# MCU.net
KiCad netlist of a schematic drawn in Altium Designer
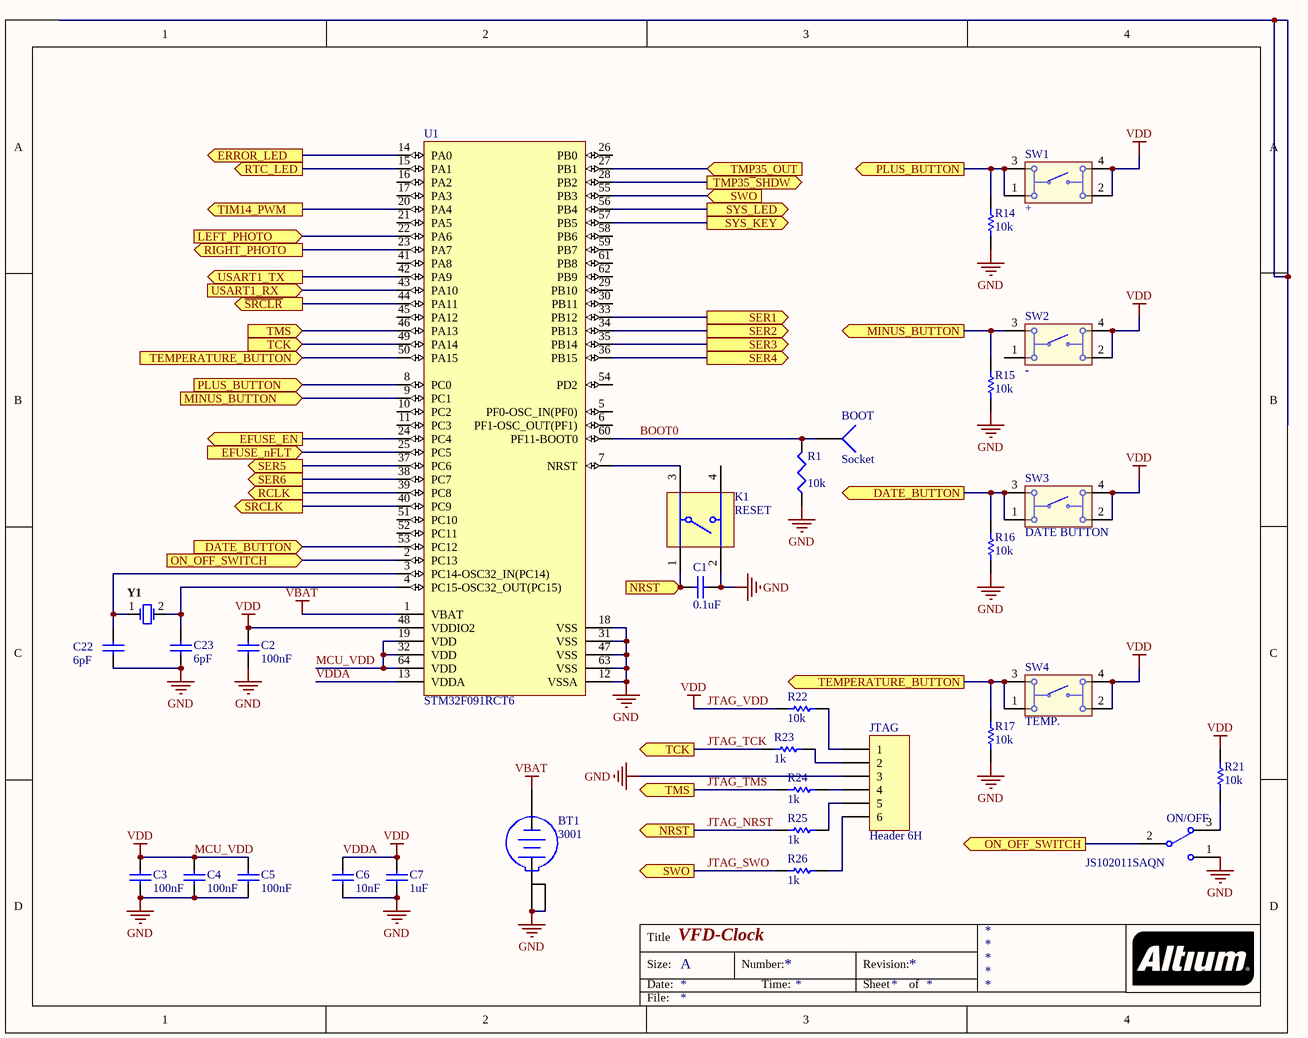
[diagram p0: MCU.SchDoc]

(export (version "E")
  (design (tool "Eeschema 10.0.6"))
  (components
    (comp (ref "BOOT")
      (value "Socket")
      (footprint "PIN1")
      (fields (field (name "PUBLISHER") "Altium Limited"))
      (libsource (lib "Miscellaneous Connectors") (part "Socket"))
    )
    (comp (ref "BT1")
      (value "3001")
      (footprint "KSTN-3001_V")
      (description "Holder Battery Coin, 12 mm, 2-Pin THD, RoHS")
      (fields (field (name "MANUFACTURER") "Keystone"))
      (libsource (lib "Altium Content Vault") (part "BATTERY-HOLDER-COIN-3"))
    )
    (comp (ref "C1")
      (value "0.1uF")
      (footprint "CAPC1608X90X40ML10T20")
      (fields (field (name "TOLERANCE") "±10%") (field (name "MANUFACTURER") "Yageo"))
      (libsource (lib "Altium Content Vault") (part "CAP-NP-2"))
    )
    (comp (ref "C2")
      (value "100nF")
      (footprint "CAPC1608X90X40ML10T20")
      (fields (field (name "TOLERANCE") "±10%") (field (name "MANUFACTURER") "Yageo"))
      (libsource (lib "Altium Content Vault") (part "CAP-NP-2"))
    )
    (comp (ref "C3")
      (value "100nF")
      (footprint "CAPC1608X90X40ML10T20")
      (fields (field (name "TOLERANCE") "±10%") (field (name "MANUFACTURER") "Yageo"))
      (libsource (lib "Altium Content Vault") (part "CAP-NP-2"))
    )
    (comp (ref "C4")
      (value "100nF")
      (footprint "CAPC1608X90X40ML10T20")
      (fields (field (name "TOLERANCE") "±10%") (field (name "MANUFACTURER") "Yageo"))
      (libsource (lib "Altium Content Vault") (part "CAP-NP-2"))
    )
    (comp (ref "C5")
      (value "100nF")
      (footprint "CAPC1608X90X40ML10T20")
      (fields (field (name "TOLERANCE") "±10%") (field (name "MANUFACTURER") "Yageo"))
      (libsource (lib "Altium Content Vault") (part "CAP-NP-2"))
    )
    (comp (ref "C6")
      (value "10nF")
      (footprint "CAPC1608X90X40ML10T20")
      (description "Chip Capacitor, 10 nF, +/- 10%, 50 V, -55 to 125 degC, 0603 (1608 Metric), RoHS, Tape and Reel")
      (fields (field (name "MANUFACTURER") "Yageo") (field (name "TOLERANCE") "10%"))
      (libsource (lib "Altium Content Vault") (part "CAP-NP-2"))
    )
    (comp (ref "C7")
      (value "1uF")
      (footprint "CAPC1608X90X20LL10")
      (description "Chip Capacitor, 1 uF, +/- 10%, 50 V, -55 to 85 degC, 0603 (1608 Metric), RoHS, Tape and Reel")
      (fields
        (field (name "MANUFACTURER") "TDK")
        (field (name "PCN PART NUMBER") "MLCCPartNumberChange30/Nov/2012")
      )
      (libsource (lib "Altium Content Vault") (part "CAP-NP-2"))
    )
    (comp (ref "C22")
      (value "6pF")
      (footprint "CAPC1608X90X40ML10T20")
      (fields (field (name "TOLERANCE") "±10%") (field (name "MANUFACTURER") "Yageo"))
      (libsource (lib "Altium Content Vault") (part "CAP-NP-2"))
    )
    (comp (ref "C23")
      (value "6pF")
      (footprint "CAPC1608X90X40ML10T20")
      (fields (field (name "TOLERANCE") "±10%") (field (name "MANUFACTURER") "Yageo"))
      (libsource (lib "Altium Content Vault") (part "CAP-NP-2"))
    )
    (comp (ref "JTAG")
      (value "Header 6H")
      (footprint "HDR1X6H")
      (description "Header, 6-Pin, Right Angle")
      (fields (field (name "PUBLISHER") "Altium Limited"))
      (libsource (lib "Miscellaneous Connectors") (part "Header 6H"))
    )
    (comp (ref "K1")
      (value "RESET")
      (footprint "PNSC-EVPAA_V")
      (description "Light Touch Switch, 100 mOhm, -40 to 85 degC, 4-Pin SMD, RoHS, Tape and Reel")
      (fields (field (name "MANUFACTURER") "Panasonic") (field (name "PART NO") "EVP-AA002K"))
      (libsource (lib "VFD_Clock_lib") (part "CMP-2000-06231-1"))
    )
    (comp (ref "ON/OFF")
      (value "JS102011SAQN")
      (footprint "CKCP-JS102011SAQN-3_V")
      (description "Sub-Miniature Slide Switch, SPDT, -40 to 85 degC, 3-Pin SMD, RoHS, Tape and Reel")
      (fields (field (name "MANUFACTURER") "C&K Components"))
      (libsource (lib "Altium Content Vault") (part "SW-SPDT-3"))
    )
    (comp (ref "R1")
      (value "10k")
      (footprint "J1-0603")
      (description "Resistor")
      (fields (field (name "PUBLISHER") "Altium Limited"))
      (libsource (lib "Miscellaneous Devices") (part "Res3"))
    )
    (comp (ref "R14")
      (value "10k")
      (footprint "RESC1608X55X30LL20T20")
      (fields (field (name "MANUFACTURER") "Panasonic") (field (name "PART NUMBER") "ERA3AEB102V"))
      (libsource (lib "Altium Content Vault") (part "RES"))
    )
    (comp (ref "R15")
      (value "10k")
      (footprint "RESC1608X55X30LL20T20")
      (fields (field (name "MANUFACTURER") "Panasonic") (field (name "PART NUMBER") "ERA3AEB102V"))
      (libsource (lib "Altium Content Vault") (part "RES"))
    )
    (comp (ref "R16")
      (value "10k")
      (footprint "RESC1608X55X30LL20T20")
      (fields (field (name "MANUFACTURER") "Panasonic") (field (name "PART NUMBER") "ERA3AEB102V"))
      (libsource (lib "Altium Content Vault") (part "RES"))
    )
    (comp (ref "R17")
      (value "10k")
      (footprint "RESC1608X55X30LL20T20")
      (fields (field (name "MANUFACTURER") "Panasonic") (field (name "PART NUMBER") "ERA3AEB102V"))
      (libsource (lib "Altium Content Vault") (part "RES"))
    )
    (comp (ref "R21")
      (value "10k")
      (footprint "RESC1608X55X30LL20T20")
      (fields (field (name "MANUFACTURER") "Panasonic") (field (name "PART NUMBER") "ERA3AEB102V"))
      (libsource (lib "Altium Content Vault") (part "RES"))
    )
    (comp (ref "R22")
      (value "10k")
      (footprint "RESC1608X55X30LL20T20")
      (fields (field (name "MANUFACTURER") "Panasonic") (field (name "PART NUMBER") "ERA3AEB102V"))
      (libsource (lib "Altium Content Vault") (part "RES"))
    )
    (comp (ref "R23")
      (value "1k")
      (footprint "RESC1608X55X30LL20T20")
      (fields (field (name "MANUFACTURER") "Panasonic") (field (name "PART NUMBER") "ERA3AEB102V"))
      (libsource (lib "Altium Content Vault") (part "RES"))
    )
    (comp (ref "R24")
      (value "1k")
      (footprint "RESC1608X55X30LL20T20")
      (fields (field (name "MANUFACTURER") "Panasonic") (field (name "PART NUMBER") "ERA3AEB102V"))
      (libsource (lib "Altium Content Vault") (part "RES"))
    )
    (comp (ref "R25")
      (value "1k")
      (footprint "RESC1608X55X30LL20T20")
      (fields (field (name "MANUFACTURER") "Panasonic") (field (name "PART NUMBER") "ERA3AEB102V"))
      (libsource (lib "Altium Content Vault") (part "RES"))
    )
    (comp (ref "R26")
      (value "1k")
      (footprint "RESC1608X55X30LL20T20")
      (fields (field (name "MANUFACTURER") "Panasonic") (field (name "PART NUMBER") "ERA3AEB102V"))
      (libsource (lib "Altium Content Vault") (part "RES"))
    )
    (comp (ref "SW1")
      (value "+")
      (footprint "434331045822")
      (description "WS-TASU SMD Tact Switch 4.7X3.5 mm side push")
      (fields (field (name "PARTNUMBER") "434331045822") (field (name "MANUFACTURER") "Wuerth Elektronik"))
      (libsource (lib "Altium Content Vault") (part "WE-TACT-SW-4"))
    )
    (comp (ref "SW2")
      (value "-")
      (footprint "434331045822")
      (description "WS-TASU SMD Tact Switch 4.7X3.5 mm side push")
      (fields (field (name "PARTNUMBER") "434331045822") (field (name "MANUFACTURER") "Wuerth Elektronik"))
      (libsource (lib "Altium Content Vault") (part "WE-TACT-SW-4"))
    )
    (comp (ref "SW3")
      (value "DATE BUTTON")
      (footprint "434331045822")
      (description "WS-TASU SMD Tact Switch 4.7X3.5 mm side push")
      (fields (field (name "PARTNUMBER") "434331045822") (field (name "MANUFACTURER") "Wuerth Elektronik"))
      (libsource (lib "Altium Content Vault") (part "WE-TACT-SW-4"))
    )
    (comp (ref "SW4")
      (value "TEMP.")
      (footprint "434331045822")
      (description "WS-TASU SMD Tact Switch 4.7X3.5 mm side push")
      (fields (field (name "PARTNUMBER") "434331045822") (field (name "MANUFACTURER") "Wuerth Elektronik"))
      (libsource (lib "Altium Content Vault") (part "WE-TACT-SW-4"))
    )
    (comp (ref "U1")
      (value "STM32F091RCT6")
      (footprint "STM-LQFP64_L")
      (fields (field (name "MANUFACTURER") "STMicroelectronics"))
      (libsource (lib "Altium Content Vault") (part "MC-ARM-STM32F091-LQFP64"))
    )
    (comp (ref "Y1")
      (value "ABS07-120-32.768KHZ-T")
      (footprint "ABRA-ABS07_A_V")
      (description "Tuning Fork Crystal, 32.768 KHz, +/- 20 ppm, -40 to 85 degC, 2-Pin SMD, RoHS, Tape and Reel")
      (fields (field (name "MANUFACTURER") "Abracon") (field (name "TOLERANCE") "20ppm"))
      (libsource (lib "Altium Content Vault") (part "XTAL-1-2-2"))
    )
  )
  (nets
    (net (code "1") (name "/BOOT0") (class "Default")
      (node (ref "BOOT") (pin "1") (pinfunction "1_1") (pintype "passive"))
      (node (ref "R1") (pin "2") (pinfunction "2_2") (pintype "passive"))
      (node (ref "U1") (pin "60") (pinfunction "PF11-BOOT0_60") (pintype "bidirectional"))
    )
    (net (code "2") (name "/DATE_BUTTON") (class "Default")
      (node (ref "R16") (pin "2") (pinfunction "2_2") (pintype "passive"))
      (node (ref "SW3") (pin "1") (pinfunction "1_1") (pintype "passive"))
      (node (ref "SW3") (pin "3") (pinfunction "3_3") (pintype "passive"))
      (node (ref "U1") (pin "53") (pinfunction "PC12_53") (pintype "bidirectional"))
    )
    (net (code "3") (name "/EFUSE_EN") (class "Default")
      (node (ref "U1") (pin "24") (pinfunction "PC4_24") (pintype "bidirectional"))
    )
    (net (code "4") (name "/EFUSE_nFLT") (class "Default")
      (node (ref "U1") (pin "25") (pinfunction "PC5_25") (pintype "bidirectional"))
    )
    (net (code "5") (name "/ERROR_LED") (class "Default")
      (node (ref "U1") (pin "14") (pinfunction "PA0_14") (pintype "bidirectional"))
    )
    (net (code "6") (name "/JTAG_NRST") (class "Default")
      (node (ref "C1") (pin "1") (pinfunction "1_1") (pintype "passive"))
      (node (ref "K1") (pin "1") (pinfunction "A_1") (pintype "passive"))
      (node (ref "R25") (pin "2") (pinfunction "2_2") (pintype "passive"))
    )
    (net (code "7") (name "/JTAG_SWO") (class "Default")
      (node (ref "R26") (pin "2") (pinfunction "2_2") (pintype "passive"))
      (node (ref "U1") (pin "55") (pinfunction "PB3_55") (pintype "bidirectional"))
    )
    (net (code "8") (name "/JTAG_TCK") (class "Default")
      (node (ref "R23") (pin "2") (pinfunction "2_2") (pintype "passive"))
      (node (ref "U1") (pin "49") (pinfunction "PA14_49") (pintype "bidirectional"))
    )
    (net (code "9") (name "/JTAG_TMS") (class "Default")
      (node (ref "R24") (pin "2") (pinfunction "2_2") (pintype "passive"))
      (node (ref "U1") (pin "46") (pinfunction "PA13_46") (pintype "bidirectional"))
    )
    (net (code "10") (name "/LEFT_PHOTO") (class "Default")
      (node (ref "U1") (pin "22") (pinfunction "PA6_22") (pintype "bidirectional"))
    )
    (net (code "11") (name "/MINUS_BUTTON") (class "Default")
      (node (ref "R15") (pin "2") (pinfunction "2_2") (pintype "passive"))
      (node (ref "SW2") (pin "3") (pinfunction "3_3") (pintype "passive"))
      (node (ref "U1") (pin "9") (pinfunction "PC1_9") (pintype "bidirectional"))
    )
    (net (code "12") (name "/ON_OFF_SWITCH") (class "Default")
      (node (ref "ON/OFF") (pin "2") (pinfunction "2_2") (pintype "passive"))
      (node (ref "U1") (pin "2") (pinfunction "PC13_2") (pintype "bidirectional"))
    )
    (net (code "13") (name "/PLUS_BUTTON") (class "Default")
      (node (ref "R14") (pin "2") (pinfunction "2_2") (pintype "passive"))
      (node (ref "SW1") (pin "1") (pinfunction "1_1") (pintype "passive"))
      (node (ref "SW1") (pin "3") (pinfunction "3_3") (pintype "passive"))
      (node (ref "U1") (pin "8") (pinfunction "PC0_8") (pintype "bidirectional"))
    )
    (net (code "14") (name "/RCLK") (class "Default")
      (node (ref "U1") (pin "39") (pinfunction "PC8_39") (pintype "bidirectional"))
    )
    (net (code "15") (name "/RIGHT_PHOTO") (class "Default")
      (node (ref "U1") (pin "23") (pinfunction "PA7_23") (pintype "bidirectional"))
    )
    (net (code "16") (name "/RTC_LED") (class "Default")
      (node (ref "U1") (pin "15") (pinfunction "PA1_15") (pintype "bidirectional"))
    )
    (net (code "17") (name "/SER1") (class "Default")
      (node (ref "U1") (pin "33") (pinfunction "PB12_33") (pintype "bidirectional"))
    )
    (net (code "18") (name "/SER2") (class "Default")
      (node (ref "U1") (pin "34") (pinfunction "PB13_34") (pintype "bidirectional"))
    )
    (net (code "19") (name "/SER3") (class "Default")
      (node (ref "U1") (pin "35") (pinfunction "PB14_35") (pintype "bidirectional"))
    )
    (net (code "20") (name "/SER4") (class "Default")
      (node (ref "U1") (pin "36") (pinfunction "PB15_36") (pintype "bidirectional"))
    )
    (net (code "21") (name "/SER5") (class "Default")
      (node (ref "U1") (pin "37") (pinfunction "PC6_37") (pintype "bidirectional"))
    )
    (net (code "22") (name "/SER6") (class "Default")
      (node (ref "U1") (pin "38") (pinfunction "PC7_38") (pintype "bidirectional"))
    )
    (net (code "23") (name "/SRCLK") (class "Default")
      (node (ref "U1") (pin "40") (pinfunction "PC9_40") (pintype "bidirectional"))
    )
    (net (code "24") (name "/SRCLR") (class "Default")
      (node (ref "U1") (pin "44") (pinfunction "PA11_44") (pintype "bidirectional"))
    )
    (net (code "25") (name "/SYS_KEY") (class "Default")
      (node (ref "U1") (pin "57") (pinfunction "PB5_57") (pintype "bidirectional"))
    )
    (net (code "26") (name "/SYS_LED") (class "Default")
      (node (ref "U1") (pin "56") (pinfunction "PB4_56") (pintype "bidirectional"))
    )
    (net (code "27") (name "/TEMPERATURE_BUTTON") (class "Default")
      (node (ref "R17") (pin "2") (pinfunction "2_2") (pintype "passive"))
      (node (ref "SW4") (pin "1") (pinfunction "1_1") (pintype "passive"))
      (node (ref "SW4") (pin "3") (pinfunction "3_3") (pintype "passive"))
      (node (ref "U1") (pin "50") (pinfunction "PA15_50") (pintype "bidirectional"))
    )
    (net (code "28") (name "/TIM14_PWM") (class "Default")
      (node (ref "U1") (pin "20") (pinfunction "PA4_20") (pintype "bidirectional"))
    )
    (net (code "29") (name "/TMP35_OUT") (class "Default")
      (node (ref "U1") (pin "27") (pinfunction "PB1_27") (pintype "bidirectional"))
    )
    (net (code "30") (name "/TMP35~{_}SHDW") (class "Default")
      (node (ref "U1") (pin "28") (pinfunction "PB2_28") (pintype "bidirectional"))
    )
    (net (code "31") (name "/USART1_RX") (class "Default")
      (node (ref "U1") (pin "43") (pinfunction "PA10_43") (pintype "bidirectional"))
    )
    (net (code "32") (name "/USART1_TX") (class "Default")
      (node (ref "U1") (pin "42") (pinfunction "PA9_42") (pintype "bidirectional"))
    )
    (net (code "33") (name "GND") (class "Default")
      (node (ref "BT1") (pin "1") (pinfunction "+_1") (pintype "passive"))
      (node (ref "BT1") (pin "2") (pinfunction "+_2") (pintype "passive"))
      (node (ref "C1") (pin "2") (pinfunction "2_2") (pintype "passive"))
      (node (ref "C2") (pin "1") (pinfunction "1_1") (pintype "passive"))
      (node (ref "C22") (pin "1") (pinfunction "1_1") (pintype "passive"))
      (node (ref "C23") (pin "1") (pinfunction "1_1") (pintype "passive"))
      (node (ref "C3") (pin "1") (pinfunction "1_1") (pintype "passive"))
      (node (ref "C4") (pin "1") (pinfunction "1_1") (pintype "passive"))
      (node (ref "C5") (pin "1") (pinfunction "1_1") (pintype "passive"))
      (node (ref "C6") (pin "2") (pinfunction "2_2") (pintype "passive"))
      (node (ref "C7") (pin "1") (pinfunction "1_1") (pintype "passive"))
      (node (ref "JTAG") (pin "3") (pinfunction "3_3") (pintype "passive"))
      (node (ref "K1") (pin "2") (pinfunction "B_2") (pintype "passive"))
      (node (ref "ON/OFF") (pin "1") (pinfunction "1_1") (pintype "passive"))
      (node (ref "R1") (pin "1") (pinfunction "1_1") (pintype "passive"))
      (node (ref "R14") (pin "1") (pinfunction "1_1") (pintype "passive"))
      (node (ref "R15") (pin "1") (pinfunction "1_1") (pintype "passive"))
      (node (ref "R16") (pin "1") (pinfunction "1_1") (pintype "passive"))
      (node (ref "R17") (pin "1") (pinfunction "1_1") (pintype "passive"))
      (node (ref "U1") (pin "12") (pinfunction "VSSA_12") (pintype "power_in"))
      (node (ref "U1") (pin "18") (pinfunction "VSS_18") (pintype "power_in"))
      (node (ref "U1") (pin "31") (pinfunction "VSS_31") (pintype "power_in"))
      (node (ref "U1") (pin "47") (pinfunction "VSS_47") (pintype "power_in"))
      (node (ref "U1") (pin "63") (pinfunction "VSS_63") (pintype "power_in"))
    )
    (net (code "34") (name "Net-(JTAG-Pad1)") (class "Default")
      (node (ref "JTAG") (pin "1") (pinfunction "1_1") (pintype "passive"))
      (node (ref "R22") (pin "1") (pinfunction "1_1") (pintype "passive"))
    )
    (net (code "35") (name "Net-(JTAG-Pad2)") (class "Default")
      (node (ref "JTAG") (pin "2") (pinfunction "2_2") (pintype "passive"))
      (node (ref "R23") (pin "1") (pinfunction "1_1") (pintype "passive"))
    )
    (net (code "36") (name "Net-(JTAG-Pad4)") (class "Default")
      (node (ref "JTAG") (pin "4") (pinfunction "4_4") (pintype "passive"))
      (node (ref "R24") (pin "1") (pinfunction "1_1") (pintype "passive"))
    )
    (net (code "37") (name "Net-(JTAG-Pad5)") (class "Default")
      (node (ref "JTAG") (pin "5") (pinfunction "5_5") (pintype "passive"))
      (node (ref "R25") (pin "1") (pinfunction "1_1") (pintype "passive"))
    )
    (net (code "38") (name "Net-(JTAG-Pad6)") (class "Default")
      (node (ref "JTAG") (pin "6") (pinfunction "6_6") (pintype "passive"))
      (node (ref "R26") (pin "1") (pinfunction "1_1") (pintype "passive"))
    )
    (net (code "39") (name "Net-(K1-A')") (class "Default")
      (node (ref "K1") (pin "3") (pinfunction "A'_3") (pintype "passive"))
      (node (ref "U1") (pin "7") (pinfunction "NRST_7") (pintype "bidirectional"))
    )
    (net (code "40") (name "Net-(ON/OFF-Pad3)") (class "Default")
      (node (ref "ON/OFF") (pin "3") (pinfunction "3_3") (pintype "passive"))
      (node (ref "R21") (pin "1") (pinfunction "1_1") (pintype "passive"))
    )
    (net (code "41") (name "Net-(U1-PC14-OSC32_IN(PC14))") (class "Default")
      (node (ref "C22") (pin "2") (pinfunction "2_2") (pintype "passive"))
      (node (ref "U1") (pin "3") (pinfunction "PC14-OSC32_IN(PC14)_3") (pintype "bidirectional"))
      (node (ref "Y1") (pin "1") (pinfunction "1_1") (pintype "passive"))
    )
    (net (code "42") (name "Net-(U1-PC15-OSC32_OUT(PC15))") (class "Default")
      (node (ref "C23") (pin "2") (pinfunction "2_2") (pintype "passive"))
      (node (ref "U1") (pin "4") (pinfunction "PC15-OSC32_OUT(PC15)_4") (pintype "bidirectional"))
      (node (ref "Y1") (pin "2") (pinfunction "2_2") (pintype "passive"))
    )
    (net (code "43") (name "VBAT") (class "Default")
      (node (ref "BT1") (pin "3") (pinfunction "-_3") (pintype "passive"))
      (node (ref "U1") (pin "1") (pinfunction "VBAT_1") (pintype "power_in"))
    )
    (net (code "44") (name "VDD") (class "Default")
      (node (ref "C2") (pin "2") (pinfunction "2_2") (pintype "passive"))
      (node (ref "C3") (pin "2") (pinfunction "2_2") (pintype "passive"))
      (node (ref "C4") (pin "2") (pinfunction "2_2") (pintype "passive"))
      (node (ref "C5") (pin "2") (pinfunction "2_2") (pintype "passive"))
      (node (ref "C6") (pin "1") (pinfunction "1_1") (pintype "passive"))
      (node (ref "C7") (pin "2") (pinfunction "2_2") (pintype "passive"))
      (node (ref "R21") (pin "2") (pinfunction "2_2") (pintype "passive"))
      (node (ref "R22") (pin "2") (pinfunction "2_2") (pintype "passive"))
      (node (ref "SW1") (pin "2") (pinfunction "2_2") (pintype "passive"))
      (node (ref "SW1") (pin "4") (pinfunction "4_4") (pintype "passive"))
      (node (ref "SW2") (pin "2") (pinfunction "2_2") (pintype "passive"))
      (node (ref "SW2") (pin "4") (pinfunction "4_4") (pintype "passive"))
      (node (ref "SW3") (pin "2") (pinfunction "2_2") (pintype "passive"))
      (node (ref "SW3") (pin "4") (pinfunction "4_4") (pintype "passive"))
      (node (ref "SW4") (pin "2") (pinfunction "2_2") (pintype "passive"))
      (node (ref "SW4") (pin "4") (pinfunction "4_4") (pintype "passive"))
      (node (ref "U1") (pin "13") (pinfunction "VDDA_13") (pintype "power_in"))
      (node (ref "U1") (pin "19") (pinfunction "VDD_19") (pintype "power_in"))
      (node (ref "U1") (pin "32") (pinfunction "VDD_32") (pintype "power_in"))
      (node (ref "U1") (pin "48") (pinfunction "VDDIO2_48") (pintype "power_in"))
      (node (ref "U1") (pin "64") (pinfunction "VDD_64") (pintype "power_in"))
    )
    (net (code "45") (name "unconnected-(K1-B'-Pad4)") (class "Default")
      (node (ref "K1") (pin "4") (pinfunction "B'_4") (pintype "passive"))
    )
    (net (code "46") (name "unconnected-(SW2-Pad1)") (class "Default")
      (node (ref "SW2") (pin "1") (pinfunction "1_1") (pintype "passive"))
    )
    (net (code "47") (name "unconnected-(U1-PA2-Pad16)") (class "Default")
      (node (ref "U1") (pin "16") (pinfunction "PA2_16") (pintype "bidirectional"))
    )
    (net (code "48") (name "unconnected-(U1-PA3-Pad17)") (class "Default")
      (node (ref "U1") (pin "17") (pinfunction "PA3_17") (pintype "bidirectional"))
    )
    (net (code "49") (name "unconnected-(U1-PA5-Pad21)") (class "Default")
      (node (ref "U1") (pin "21") (pinfunction "PA5_21") (pintype "bidirectional"))
    )
    (net (code "50") (name "unconnected-(U1-PA8-Pad41)") (class "Default")
      (node (ref "U1") (pin "41") (pinfunction "PA8_41") (pintype "bidirectional"))
    )
    (net (code "51") (name "unconnected-(U1-PA12-Pad45)") (class "Default")
      (node (ref "U1") (pin "45") (pinfunction "PA12_45") (pintype "bidirectional"))
    )
    (net (code "52") (name "unconnected-(U1-PB0-Pad26)") (class "Default")
      (node (ref "U1") (pin "26") (pinfunction "PB0_26") (pintype "bidirectional"))
    )
    (net (code "53") (name "unconnected-(U1-PB6-Pad58)") (class "Default")
      (node (ref "U1") (pin "58") (pinfunction "PB6_58") (pintype "bidirectional"))
    )
    (net (code "54") (name "unconnected-(U1-PB7-Pad59)") (class "Default")
      (node (ref "U1") (pin "59") (pinfunction "PB7_59") (pintype "bidirectional"))
    )
    (net (code "55") (name "unconnected-(U1-PB8-Pad61)") (class "Default")
      (node (ref "U1") (pin "61") (pinfunction "PB8_61") (pintype "bidirectional"))
    )
    (net (code "56") (name "unconnected-(U1-PB9-Pad62)") (class "Default")
      (node (ref "U1") (pin "62") (pinfunction "PB9_62") (pintype "bidirectional"))
    )
    (net (code "57") (name "unconnected-(U1-PB10-Pad29)") (class "Default")
      (node (ref "U1") (pin "29") (pinfunction "PB10_29") (pintype "bidirectional"))
    )
    (net (code "58") (name "unconnected-(U1-PB11-Pad30)") (class "Default")
      (node (ref "U1") (pin "30") (pinfunction "PB11_30") (pintype "bidirectional"))
    )
    (net (code "59") (name "unconnected-(U1-PC2-Pad10)") (class "Default")
      (node (ref "U1") (pin "10") (pinfunction "PC2_10") (pintype "bidirectional"))
    )
    (net (code "60") (name "unconnected-(U1-PC3-Pad11)") (class "Default")
      (node (ref "U1") (pin "11") (pinfunction "PC3_11") (pintype "bidirectional"))
    )
    (net (code "61") (name "unconnected-(U1-PC10-Pad51)") (class "Default")
      (node (ref "U1") (pin "51") (pinfunction "PC10_51") (pintype "bidirectional"))
    )
    (net (code "62") (name "unconnected-(U1-PC11-Pad52)") (class "Default")
      (node (ref "U1") (pin "52") (pinfunction "PC11_52") (pintype "bidirectional"))
    )
    (net (code "63") (name "unconnected-(U1-PD2-Pad54)") (class "Default")
      (node (ref "U1") (pin "54") (pinfunction "PD2_54") (pintype "bidirectional"))
    )
    (net (code "64") (name "unconnected-(U1-PF0-OSC_IN(PF0)-Pad5)") (class "Default")
      (node (ref "U1") (pin "5") (pinfunction "PF0-OSC_IN(PF0)_5") (pintype "bidirectional"))
    )
    (net (code "65") (name "unconnected-(U1-PF1-OSC_OUT(PF1)-Pad6)") (class "Default")
      (node (ref "U1") (pin "6") (pinfunction "PF1-OSC_OUT(PF1)_6") (pintype "bidirectional"))
    )
  )
)
